# VOLT_REG_SCH.net
KiCad netlist of a schematic drawn in Altium Designer
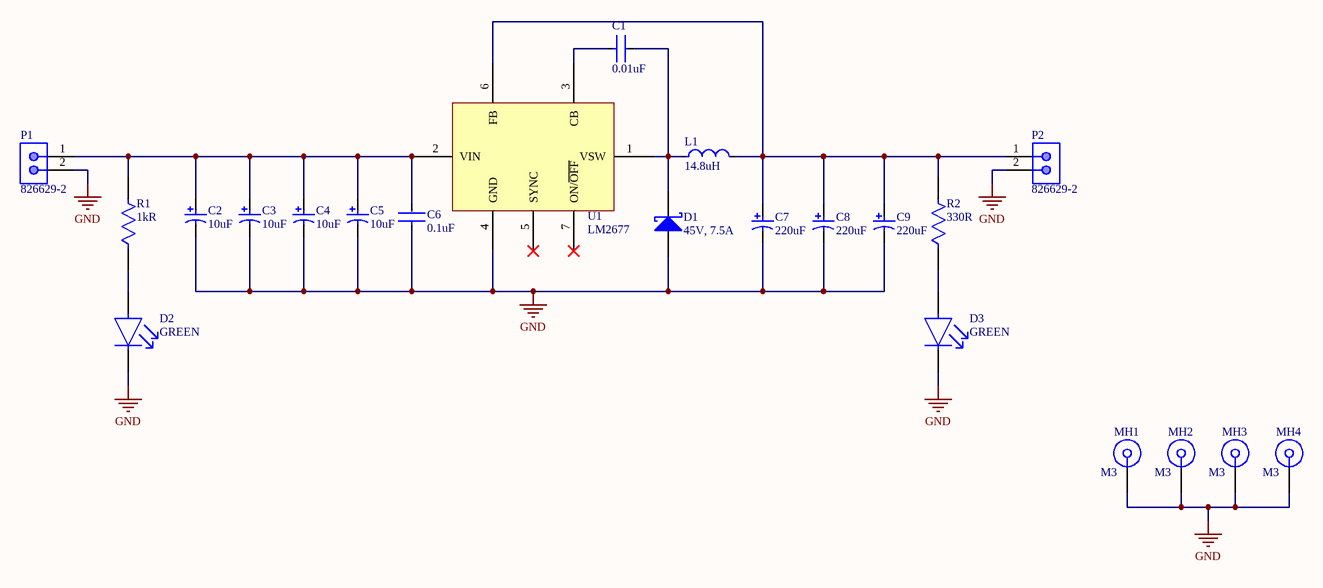
[diagram p0: VOLT_REG_SCH.SchDoc]

(export (version "E")
  (design (tool "Eeschema 10.0.6"))
  (components
    (comp (ref "C1")
      (value "0.01uF")
      (footprint "CAP_1206_AVX_1206")
      (description "±10% 50V Ceramic Capacitor X7R 1206 (3216 Metric)")
      (fields
        (field (name "MANUFACTURER") "AVX Corporation")
        (field (name "MANUFACTURER PART NUMBER") "12065C103KAT2A")
      )
      (libsource (lib "VOLT_REG_INT_LIB") (part "CAP_0.01uF_10%_50V"))
    )
    (comp (ref "C2")
      (value "10uF")
      (footprint "CAP_2917_KEMT_T495_D")
      (description "Molded Tantalum Capacitors 2917 (7343 Metric) 260mOhm")
      (fields
        (field (name "MANUFACTURER") "KEMET")
        (field (name "MANUFACTURER PART NUMBER") "T495D106K035ATE260")
      )
      (libsource (lib "VOLT_REG_INT_LIB") (part "PCAP_10uF_10%_35V"))
    )
    (comp (ref "C3")
      (value "10uF")
      (footprint "CAP_2917_KEMT_T495_D")
      (description "Molded Tantalum Capacitors 2917 (7343 Metric) 260mOhm")
      (fields
        (field (name "MANUFACTURER") "KEMET")
        (field (name "MANUFACTURER PART NUMBER") "T495D106K035ATE260")
      )
      (libsource (lib "VOLT_REG_INT_LIB") (part "PCAP_10uF_10%_35V"))
    )
    (comp (ref "C4")
      (value "10uF")
      (footprint "CAP_2917_KEMT_T495_D")
      (description "Molded Tantalum Capacitors 2917 (7343 Metric) 260mOhm")
      (fields
        (field (name "MANUFACTURER") "KEMET")
        (field (name "MANUFACTURER PART NUMBER") "T495D106K035ATE260")
      )
      (libsource (lib "VOLT_REG_INT_LIB") (part "PCAP_10uF_10%_35V"))
    )
    (comp (ref "C5")
      (value "10uF")
      (footprint "CAP_2917_KEMT_T495_D")
      (description "Molded Tantalum Capacitors 2917 (7343 Metric) 260mOhm")
      (fields
        (field (name "MANUFACTURER") "KEMET")
        (field (name "MANUFACTURER PART NUMBER") "T495D106K035ATE260")
      )
      (libsource (lib "VOLT_REG_INT_LIB") (part "PCAP_10uF_10%_35V"))
    )
    (comp (ref "C6")
      (value "0.1uF")
      (footprint "CAP_1206_AVX_1206")
      (description "±10% 50V Ceramic Capacitor X8R 1206 (3216 Metric)")
      (fields
        (field (name "MANUFACTURER") "AVX Corporation")
        (field (name "MANUFACTURER PART NUMBER") "12065F104K4T2A")
      )
      (libsource (lib "VOLT_REG_INT_LIB") (part "CAP_0.1uF_10%_50V"))
    )
    (comp (ref "C7")
      (value "220uF")
      (footprint "CAP_2917_AVX_7343_31")
      (description "Molded Tantalum Capacitors 2917 (7343 Metric) 100mOhm")
      (fields
        (field (name "MANUFACTURER") "AVX Corporation")
        (field (name "MANUFACTURER PART NUMBER") "TPSD227M010R0100")
      )
      (libsource (lib "VOLT_REG_INT_LIB") (part "PCAP_220uF_20%_10V"))
    )
    (comp (ref "C8")
      (value "220uF")
      (footprint "CAP_2917_AVX_7343_31")
      (description "Molded Tantalum Capacitors 2917 (7343 Metric) 100mOhm")
      (fields
        (field (name "MANUFACTURER") "AVX Corporation")
        (field (name "MANUFACTURER PART NUMBER") "TPSD227M010R0100")
      )
      (libsource (lib "VOLT_REG_INT_LIB") (part "PCAP_220uF_20%_10V"))
    )
    (comp (ref "C9")
      (value "220uF")
      (footprint "CAP_2917_AVX_7343_31")
      (description "Molded Tantalum Capacitors 2917 (7343 Metric) 100mOhm")
      (fields
        (field (name "MANUFACTURER") "AVX Corporation")
        (field (name "MANUFACTURER PART NUMBER") "TPSD227M010R0100")
      )
      (libsource (lib "VOLT_REG_INT_LIB") (part "PCAP_220uF_20%_10V"))
    )
    (comp (ref "D1")
      (value "45V, 7.5A")
      (footprint "DIO_SCHOTTKY_TO_263_3_ST_D2PAK")
      (description "Diode Schottky 7.5A Surface Mount D²PAK")
      (fields
        (field (name "MANUFACTURER") "STMicroelectronics")
        (field (name "MANUFACTURER PART NUMBER") "STPS745G-TR")
      )
      (libsource (lib "VOLT_REG_INT_LIB") (part "DIO_SCHOTTKY_45V_7.5A"))
    )
    (comp (ref "D2")
      (value "GREEN")
      (footprint "DIO_1206_ LTST_C150")
      (description "LED GREEN CLEAR CHIP SMD")
      (fields
        (field (name "MANUFACTURER") "Lite-On Inc.")
        (field (name "MANUFACTURER PART NUMBER") "LTST-C150GKT")
      )
      (libsource (lib "VOLT_REG_INT_LIB") (part "DIO_LED_GREEN"))
    )
    (comp (ref "D3")
      (value "GREEN")
      (footprint "DIO_1206_ LTST_C150")
      (description "LED GREEN CLEAR CHIP SMD")
      (fields
        (field (name "MANUFACTURER") "Lite-On Inc.")
        (field (name "MANUFACTURER PART NUMBER") "LTST-C150GKT")
      )
      (libsource (lib "VOLT_REG_INT_LIB") (part "DIO_LED_GREEN"))
    )
    (comp (ref "L1")
      (value "14.8uH")
      (footprint "IND_NON_STD_LCI50")
      (description "Shielded Toroidal Inductor 27mOhm Nonstandard")
      (fields
        (field (name "MANUFACTURER") "Pulse Electronics Power")
        (field (name "MANUFACTURER PART NUMBER") "P0846SNL")
      )
      (libsource (lib "VOLT_REG_INT_LIB") (part "IND_14.8uH_20%_5A"))
    )
    (comp (ref "MH1")
      (value "M3")
      (footprint "MH_M3")
      (description "M3 Mounting Hole")
      (libsource (lib "VOLT_REG_INT_LIB") (part "MH_M3"))
    )
    (comp (ref "MH2")
      (value "M3")
      (footprint "MH_M3")
      (description "M3 Mounting Hole")
      (libsource (lib "VOLT_REG_INT_LIB") (part "MH_M3"))
    )
    (comp (ref "MH3")
      (value "M3")
      (footprint "MH_M3")
      (description "M3 Mounting Hole")
      (libsource (lib "VOLT_REG_INT_LIB") (part "MH_M3"))
    )
    (comp (ref "MH4")
      (value "M3")
      (footprint "MH_M3")
      (description "M3 Mounting Hole")
      (libsource (lib "VOLT_REG_INT_LIB") (part "MH_M3"))
    )
    (comp (ref "P1")
      (value "826629-2")
      (footprint "CONN_HEADER_MALE_0.1_2x1")
      (description "CONN HEADER VERT 2POS 2.54MM")
      (fields (field (name "MANUFACTURER") "TE Connectivity AMP Connectors"))
      (libsource (lib "VOLT_REG_INT_LIB") (part "CONN_VERT_HEADER_MALE_0.1_2x1"))
    )
    (comp (ref "P2")
      (value "826629-2")
      (footprint "CONN_HEADER_MALE_0.1_2x1")
      (description "CONN HEADER VERT 2POS 2.54MM")
      (fields (field (name "MANUFACTURER") "TE Connectivity AMP Connectors"))
      (libsource (lib "") (part "CONN_VERT_HEADER_MALE_0.1_2x1_1"))
    )
    (comp (ref "R1")
      (value "1kR")
      (footprint "RES_1206_YAGEO_RC_1206")
      (description "±1% 0.25W, 1/4W Chip Resistor 1206 (3216 Metric) Moisture Resistant Thick Film")
      (fields
        (field (name "MANUFACTURER") "Yageo")
        (field (name "MANUFACTURER PART NUMBER") "RC1206FR-071KL")
      )
      (libsource (lib "VOLT_REG_INT_LIB") (part "RES_1kR_1%_0.25W"))
    )
    (comp (ref "R2")
      (value "330R")
      (footprint "RES_1206_SE_RMCF1206")
      (description "±5% 0.25W, 1/4W Chip Resistor 1206 (3216 Metric) Automotive AEC-Q200 Thick Film")
      (fields
        (field (name "MANUFACTURER") "Stackpole Electronics Inc")
        (field (name "MANUFACTURER PART NUMBER") "RMCF1206JT330R")
      )
      (libsource (lib "VOLT_REG_INT_LIB") (part "RES_330R_5%_0.25W"))
    )
    (comp (ref "U1")
      (value "LM2677")
      (footprint "IC_TO_263_7_KTW0007B")
      (description "Buck Switching Regulator IC Positive Fixed 5V 1 Output 5A TO-220-7 (Formed Leads)")
      (fields
        (field (name "MANUFACTURER") "Texas Instruments")
        (field (name "MANUFACTURER PART NUMBER") "LM2677S-5.0/NOPB")
      )
      (libsource (lib "VOLT_REG_INT_LIB") (part "IC_LM2677"))
    )
  )
  (nets
    (net (code "1") (name "GND") (class "Default")
      (node (ref "C2") (pin "2") (pinfunction "2_2") (pintype "passive"))
      (node (ref "C3") (pin "2") (pinfunction "2_2") (pintype "passive"))
      (node (ref "C4") (pin "2") (pinfunction "2_2") (pintype "passive"))
      (node (ref "C5") (pin "2") (pinfunction "2_2") (pintype "passive"))
      (node (ref "C6") (pin "1") (pinfunction "1_1") (pintype "passive"))
      (node (ref "C7") (pin "2") (pinfunction "2_2") (pintype "passive"))
      (node (ref "C8") (pin "2") (pinfunction "2_2") (pintype "passive"))
      (node (ref "C9") (pin "2") (pinfunction "2_2") (pintype "passive"))
      (node (ref "D1") (pin "A") (pinfunction "A_A") (pintype "passive"))
      (node (ref "D2") (pin "2") (pinfunction "2_2") (pintype "passive"))
      (node (ref "D3") (pin "2") (pinfunction "2_2") (pintype "passive"))
      (node (ref "MH1") (pin "1") (pinfunction "1_1") (pintype "passive"))
      (node (ref "MH2") (pin "1") (pinfunction "1_1") (pintype "passive"))
      (node (ref "MH3") (pin "1") (pinfunction "1_1") (pintype "passive"))
      (node (ref "MH4") (pin "1") (pinfunction "1_1") (pintype "passive"))
      (node (ref "P1") (pin "2") (pinfunction "2_2") (pintype "passive"))
      (node (ref "P2") (pin "2") (pinfunction "2_2") (pintype "passive"))
      (node (ref "U1") (pin "4") (pinfunction "GND_4") (pintype "passive"))
    )
    (net (code "2") (name "Net-(D2-Pad1)") (class "Default")
      (node (ref "D2") (pin "1") (pinfunction "1_1") (pintype "passive"))
      (node (ref "R1") (pin "1") (pinfunction "1_1") (pintype "passive"))
    )
    (net (code "3") (name "Net-(D3-Pad1)") (class "Default")
      (node (ref "D3") (pin "1") (pinfunction "1_1") (pintype "passive"))
      (node (ref "R2") (pin "1") (pinfunction "1_1") (pintype "passive"))
    )
    (net (code "4") (name "Net-(U1-CB)") (class "Default")
      (node (ref "C1") (pin "1") (pinfunction "1_1") (pintype "passive"))
      (node (ref "U1") (pin "3") (pinfunction "CB_3") (pintype "passive"))
    )
    (net (code "5") (name "Net-(U1-FB)") (class "Default")
      (node (ref "C7") (pin "1") (pinfunction "1_1") (pintype "passive"))
      (node (ref "C8") (pin "1") (pinfunction "1_1") (pintype "passive"))
      (node (ref "C9") (pin "1") (pinfunction "1_1") (pintype "passive"))
      (node (ref "L1") (pin "2") (pinfunction "2_2") (pintype "passive"))
      (node (ref "P2") (pin "1") (pinfunction "1_1") (pintype "passive"))
      (node (ref "R2") (pin "2") (pinfunction "2_2") (pintype "passive"))
      (node (ref "U1") (pin "6") (pinfunction "FB_6") (pintype "passive"))
    )
    (net (code "6") (name "Net-(U1-VIN)") (class "Default")
      (node (ref "C2") (pin "1") (pinfunction "1_1") (pintype "passive"))
      (node (ref "C3") (pin "1") (pinfunction "1_1") (pintype "passive"))
      (node (ref "C4") (pin "1") (pinfunction "1_1") (pintype "passive"))
      (node (ref "C5") (pin "1") (pinfunction "1_1") (pintype "passive"))
      (node (ref "C6") (pin "2") (pinfunction "2_2") (pintype "passive"))
      (node (ref "P1") (pin "1") (pinfunction "1_1") (pintype "passive"))
      (node (ref "R1") (pin "2") (pinfunction "2_2") (pintype "passive"))
      (node (ref "U1") (pin "2") (pinfunction "VIN_2") (pintype "passive"))
    )
    (net (code "7") (name "Net-(U1-VSW)") (class "Default")
      (node (ref "C1") (pin "2") (pinfunction "2_2") (pintype "passive"))
      (node (ref "D1") (pin "K") (pinfunction "K_K") (pintype "passive"))
      (node (ref "L1") (pin "1") (pinfunction "1_1") (pintype "passive"))
      (node (ref "U1") (pin "1") (pinfunction "VSW_1") (pintype "passive"))
    )
    (net (code "8") (name "unconnected-(U1-ON{slash}~{OFF}-Pad7)") (class "Default")
      (node (ref "U1") (pin "7") (pinfunction "ON/~{OFF}_7") (pintype "passive+no_connect"))
    )
    (net (code "9") (name "unconnected-(U1-SYNC-Pad5)") (class "Default")
      (node (ref "U1") (pin "5") (pinfunction "SYNC_5") (pintype "passive+no_connect"))
    )
  )
)
